# Relay12VDC.net
KiCad netlist of a schematic drawn in Altium Designer
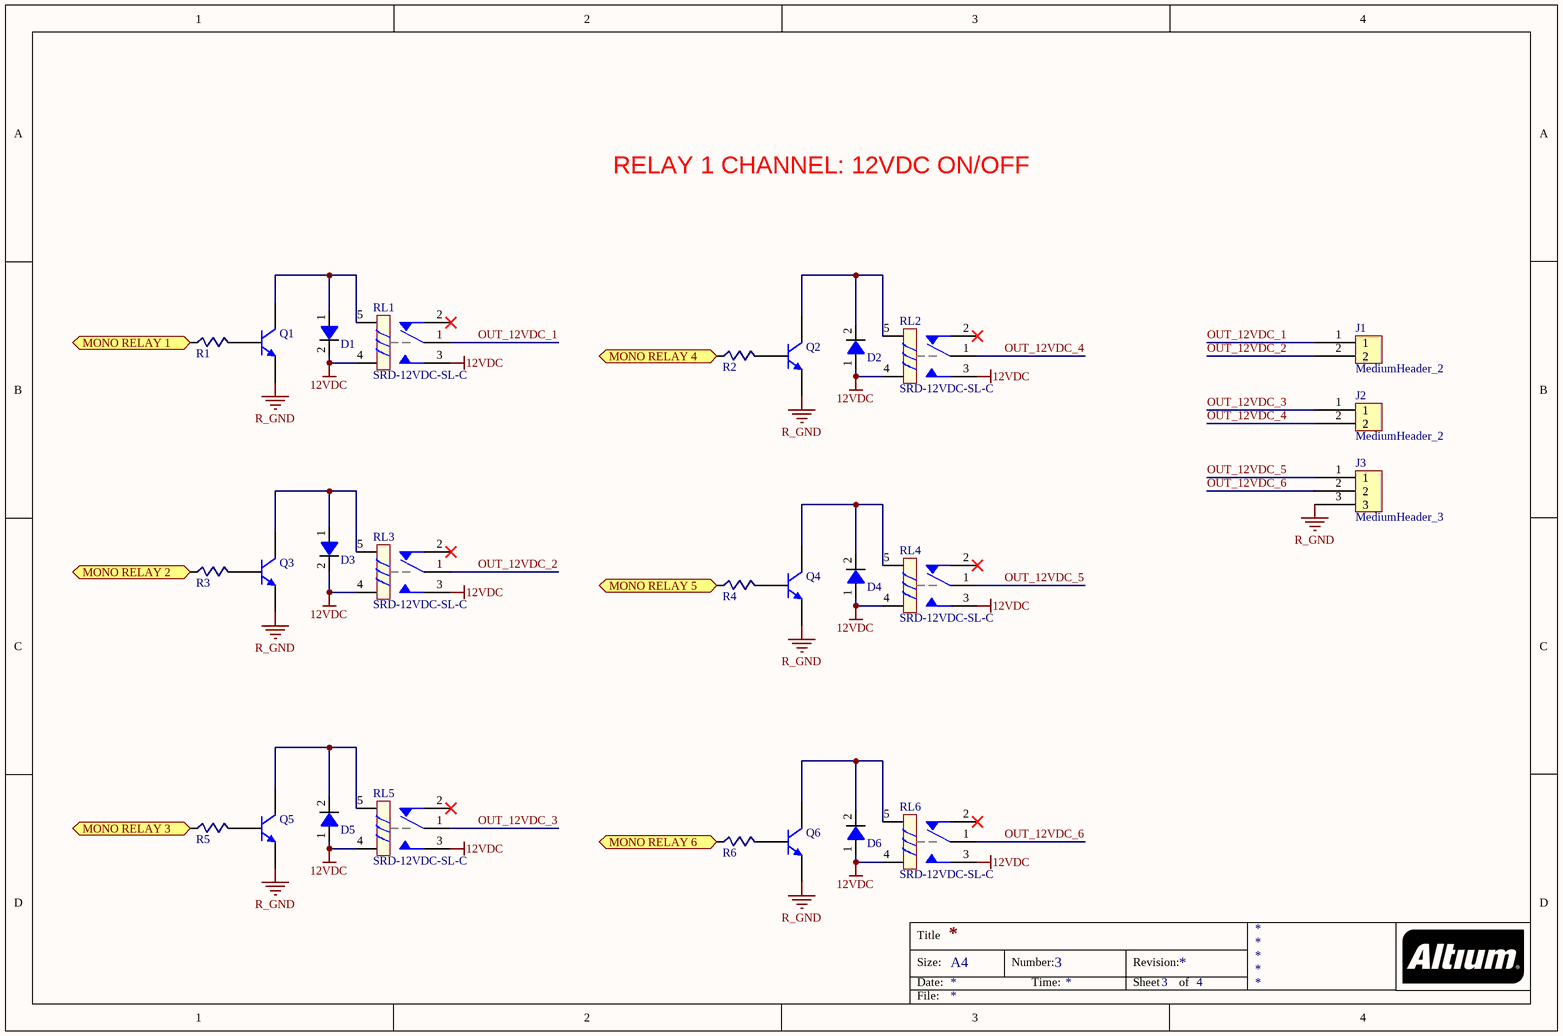
[diagram p0: Relay12VDC.SchDoc]

(export (version "E")
  (design (tool "Eeschema 10.0.6"))
  (components
    (comp (ref "D1")
      (value "M7 SMD")
      (footprint "Diode 1N4007 SMD")
      (description "DIODE GEN PURP 1KV 1A DO214AC")
      (libsource (lib "EngineersLife") (part "Diode_1N4007"))
    )
    (comp (ref "D2")
      (value "M7 SMD")
      (footprint "Diode 1N4007 SMD")
      (description "DIODE GEN PURP 1KV 1A DO214AC")
      (libsource (lib "EngineersLife") (part "Diode_1N4007"))
    )
    (comp (ref "D3")
      (value "M7 SMD")
      (footprint "Diode 1N4007 SMD")
      (description "DIODE GEN PURP 1KV 1A DO214AC")
      (libsource (lib "EngineersLife") (part "Diode_1N4007"))
    )
    (comp (ref "D4")
      (value "M7 SMD")
      (footprint "Diode 1N4007 SMD")
      (description "DIODE GEN PURP 1KV 1A DO214AC")
      (libsource (lib "EngineersLife") (part "Diode_1N4007"))
    )
    (comp (ref "D5")
      (value "M7 SMD")
      (footprint "Diode 1N4007 SMD")
      (description "DIODE GEN PURP 1KV 1A DO214AC")
      (libsource (lib "EngineersLife") (part "Diode_1N4007"))
    )
    (comp (ref "D6")
      (value "M7 SMD")
      (footprint "Diode 1N4007 SMD")
      (description "DIODE GEN PURP 1KV 1A DO214AC")
      (libsource (lib "EngineersLife") (part "Diode_1N4007"))
    )
    (comp (ref "J1")
      (value "MediumHeader_2")
      (footprint "Medium - Header 2")
      (libsource (lib "EngineersLife") (part "MediumHeader_2"))
    )
    (comp (ref "J2")
      (value "MediumHeader_2")
      (footprint "Medium - Header 2")
      (libsource (lib "EngineersLife") (part "MediumHeader_2"))
    )
    (comp (ref "J3")
      (value "MediumHeader_3")
      (footprint "Medium - Header 3")
      (libsource (lib "EngineersLife") (part "MediumHeader_3"))
    )
    (comp (ref "Q1")
      (value "MMBT3904")
      (footprint "SOT23_L_MOD")
      (description "TRANSISTOR GP NPN AMP SOT-23")
      (fields (field (name "PUBLISHER") "Altium Limited"))
      (libsource (lib "EngineersLife") (part "MMBT3904"))
    )
    (comp (ref "Q2")
      (value "MMBT3904")
      (footprint "SOT23_L_MOD")
      (description "TRANSISTOR GP NPN AMP SOT-23")
      (fields (field (name "PUBLISHER") "Altium Limited"))
      (libsource (lib "EngineersLife") (part "MMBT3904"))
    )
    (comp (ref "Q3")
      (value "MMBT3904")
      (footprint "SOT23_L_MOD")
      (description "TRANSISTOR GP NPN AMP SOT-23")
      (fields (field (name "PUBLISHER") "Altium Limited"))
      (libsource (lib "EngineersLife") (part "MMBT3904"))
    )
    (comp (ref "Q4")
      (value "MMBT3904")
      (footprint "SOT23_L_MOD")
      (description "TRANSISTOR GP NPN AMP SOT-23")
      (fields (field (name "PUBLISHER") "Altium Limited"))
      (libsource (lib "EngineersLife") (part "MMBT3904"))
    )
    (comp (ref "Q5")
      (value "MMBT3904")
      (footprint "SOT23_L_MOD")
      (description "TRANSISTOR GP NPN AMP SOT-23")
      (fields (field (name "PUBLISHER") "Altium Limited"))
      (libsource (lib "EngineersLife") (part "MMBT3904"))
    )
    (comp (ref "Q6")
      (value "MMBT3904")
      (footprint "SOT23_L_MOD")
      (description "TRANSISTOR GP NPN AMP SOT-23")
      (fields (field (name "PUBLISHER") "Altium Limited"))
      (libsource (lib "EngineersLife") (part "MMBT3904"))
    )
    (comp (ref "R1")
      (value "R_1K_0603")
      (footprint "RES-SMD-0603")
      (description "RES 1K OHM 1/10W 1% 0603 SMD")
      (libsource (lib "EngineersLife") (part "RES0603_1K"))
    )
    (comp (ref "R2")
      (value "R_1K_0603")
      (footprint "RES-SMD-0603")
      (description "RES 1K OHM 1/10W 1% 0603 SMD")
      (libsource (lib "EngineersLife") (part "RES0603_1K"))
    )
    (comp (ref "R3")
      (value "R_1K_0603")
      (footprint "RES-SMD-0603")
      (description "RES 1K OHM 1/10W 1% 0603 SMD")
      (libsource (lib "EngineersLife") (part "RES0603_1K"))
    )
    (comp (ref "R4")
      (value "R_1K_0603")
      (footprint "RES-SMD-0603")
      (description "RES 1K OHM 1/10W 1% 0603 SMD")
      (libsource (lib "EngineersLife") (part "RES0603_1K"))
    )
    (comp (ref "R5")
      (value "R_1K_0603")
      (footprint "RES-SMD-0603")
      (description "RES 1K OHM 1/10W 1% 0603 SMD")
      (libsource (lib "EngineersLife") (part "RES0603_1K"))
    )
    (comp (ref "R6")
      (value "R_1K_0603")
      (footprint "RES-SMD-0603")
      (description "RES 1K OHM 1/10W 1% 0603 SMD")
      (libsource (lib "EngineersLife") (part "RES0603_1K"))
    )
    (comp (ref "RL1")
      (value "SRD-12VDC-SL-C")
      (footprint "RELAY SRD-12VDC")
      (description "Relay SPDT,10A - 12VDC 5 Pin")
      (libsource (lib "EngineersLife") (part "RELAY SRD-12VDC"))
    )
    (comp (ref "RL2")
      (value "SRD-12VDC-SL-C")
      (footprint "RELAY SRD-12VDC")
      (description "Relay SPDT,10A - 12VDC 5 Pin")
      (libsource (lib "EngineersLife") (part "RELAY SRD-12VDC"))
    )
    (comp (ref "RL3")
      (value "SRD-12VDC-SL-C")
      (footprint "RELAY SRD-12VDC")
      (description "Relay SPDT,10A - 12VDC 5 Pin")
      (libsource (lib "EngineersLife") (part "RELAY SRD-12VDC"))
    )
    (comp (ref "RL4")
      (value "SRD-12VDC-SL-C")
      (footprint "RELAY SRD-12VDC")
      (description "Relay SPDT,10A - 12VDC 5 Pin")
      (libsource (lib "EngineersLife") (part "RELAY SRD-12VDC"))
    )
    (comp (ref "RL5")
      (value "SRD-12VDC-SL-C")
      (footprint "RELAY SRD-12VDC")
      (description "Relay SPDT,10A - 12VDC 5 Pin")
      (libsource (lib "EngineersLife") (part "RELAY SRD-12VDC"))
    )
    (comp (ref "RL6")
      (value "SRD-12VDC-SL-C")
      (footprint "RELAY SRD-12VDC")
      (description "Relay SPDT,10A - 12VDC 5 Pin")
      (libsource (lib "EngineersLife") (part "RELAY SRD-12VDC"))
    )
  )
  (nets
    (net (code "1") (name "/MONO RELAY 1") (class "Default")
      (node (ref "R1") (pin "1") (pinfunction "1_1") (pintype "passive"))
    )
    (net (code "2") (name "/MONO RELAY 2") (class "Default")
      (node (ref "R3") (pin "1") (pinfunction "1_1") (pintype "passive"))
    )
    (net (code "3") (name "/MONO RELAY 3") (class "Default")
      (node (ref "R5") (pin "1") (pinfunction "1_1") (pintype "passive"))
    )
    (net (code "4") (name "/MONO RELAY 4") (class "Default")
      (node (ref "R2") (pin "1") (pinfunction "1_1") (pintype "passive"))
    )
    (net (code "5") (name "/MONO RELAY 5") (class "Default")
      (node (ref "R4") (pin "1") (pinfunction "1_1") (pintype "passive"))
    )
    (net (code "6") (name "/MONO RELAY 6") (class "Default")
      (node (ref "R6") (pin "1") (pinfunction "1_1") (pintype "passive"))
    )
    (net (code "7") (name "/OUT_12VDC_1") (class "Default")
      (node (ref "J1") (pin "1") (pinfunction "1_1") (pintype "passive"))
      (node (ref "RL1") (pin "1") (pinfunction "1_1") (pintype "passive"))
    )
    (net (code "8") (name "/OUT_12VDC_2") (class "Default")
      (node (ref "J1") (pin "2") (pinfunction "2_2") (pintype "passive"))
      (node (ref "RL3") (pin "1") (pinfunction "1_1") (pintype "passive"))
    )
    (net (code "9") (name "/OUT_12VDC_3") (class "Default")
      (node (ref "J2") (pin "1") (pinfunction "1_1") (pintype "passive"))
      (node (ref "RL5") (pin "1") (pinfunction "1_1") (pintype "passive"))
    )
    (net (code "10") (name "/OUT_12VDC_4") (class "Default")
      (node (ref "J2") (pin "2") (pinfunction "2_2") (pintype "passive"))
      (node (ref "RL2") (pin "1") (pinfunction "1_1") (pintype "passive"))
    )
    (net (code "11") (name "/OUT_12VDC_5") (class "Default")
      (node (ref "J3") (pin "1") (pinfunction "1_1") (pintype "passive"))
      (node (ref "RL4") (pin "1") (pinfunction "1_1") (pintype "passive"))
    )
    (net (code "12") (name "/OUT_12VDC_6") (class "Default")
      (node (ref "J3") (pin "2") (pinfunction "2_2") (pintype "passive"))
      (node (ref "RL6") (pin "1") (pinfunction "1_1") (pintype "passive"))
    )
    (net (code "13") (name "12VDC") (class "Default")
      (node (ref "D1") (pin "2") (pinfunction "4_2") (pintype "passive"))
      (node (ref "D2") (pin "1") (pinfunction "3_1") (pintype "passive"))
      (node (ref "D3") (pin "2") (pinfunction "4_2") (pintype "passive"))
      (node (ref "D4") (pin "1") (pinfunction "3_1") (pintype "passive"))
      (node (ref "D5") (pin "1") (pinfunction "3_1") (pintype "passive"))
      (node (ref "D6") (pin "1") (pinfunction "3_1") (pintype "passive"))
      (node (ref "RL1") (pin "3") (pinfunction "3_3") (pintype "passive"))
      (node (ref "RL1") (pin "4") (pinfunction "4_4") (pintype "passive"))
      (node (ref "RL2") (pin "3") (pinfunction "3_3") (pintype "passive"))
      (node (ref "RL2") (pin "4") (pinfunction "4_4") (pintype "passive"))
      (node (ref "RL3") (pin "3") (pinfunction "3_3") (pintype "passive"))
      (node (ref "RL3") (pin "4") (pinfunction "4_4") (pintype "passive"))
      (node (ref "RL4") (pin "3") (pinfunction "3_3") (pintype "passive"))
      (node (ref "RL4") (pin "4") (pinfunction "4_4") (pintype "passive"))
      (node (ref "RL5") (pin "3") (pinfunction "3_3") (pintype "passive"))
      (node (ref "RL5") (pin "4") (pinfunction "4_4") (pintype "passive"))
      (node (ref "RL6") (pin "3") (pinfunction "3_3") (pintype "passive"))
      (node (ref "RL6") (pin "4") (pinfunction "4_4") (pintype "passive"))
    )
    (net (code "14") (name "Net-(D1-3)") (class "Default")
      (node (ref "D1") (pin "1") (pinfunction "3_1") (pintype "passive"))
      (node (ref "Q1") (pin "3") (pinfunction "C_3") (pintype "passive"))
      (node (ref "RL1") (pin "5") (pinfunction "5_5") (pintype "passive"))
    )
    (net (code "15") (name "Net-(D2-4)") (class "Default")
      (node (ref "D2") (pin "2") (pinfunction "4_2") (pintype "passive"))
      (node (ref "Q2") (pin "3") (pinfunction "C_3") (pintype "passive"))
      (node (ref "RL2") (pin "5") (pinfunction "5_5") (pintype "passive"))
    )
    (net (code "16") (name "Net-(D3-3)") (class "Default")
      (node (ref "D3") (pin "1") (pinfunction "3_1") (pintype "passive"))
      (node (ref "Q3") (pin "3") (pinfunction "C_3") (pintype "passive"))
      (node (ref "RL3") (pin "5") (pinfunction "5_5") (pintype "passive"))
    )
    (net (code "17") (name "Net-(D4-4)") (class "Default")
      (node (ref "D4") (pin "2") (pinfunction "4_2") (pintype "passive"))
      (node (ref "Q4") (pin "3") (pinfunction "C_3") (pintype "passive"))
      (node (ref "RL4") (pin "5") (pinfunction "5_5") (pintype "passive"))
    )
    (net (code "18") (name "Net-(D5-4)") (class "Default")
      (node (ref "D5") (pin "2") (pinfunction "4_2") (pintype "passive"))
      (node (ref "Q5") (pin "3") (pinfunction "C_3") (pintype "passive"))
      (node (ref "RL5") (pin "5") (pinfunction "5_5") (pintype "passive"))
    )
    (net (code "19") (name "Net-(D6-4)") (class "Default")
      (node (ref "D6") (pin "2") (pinfunction "4_2") (pintype "passive"))
      (node (ref "Q6") (pin "3") (pinfunction "C_3") (pintype "passive"))
      (node (ref "RL6") (pin "5") (pinfunction "5_5") (pintype "passive"))
    )
    (net (code "20") (name "Net-(Q1-B)") (class "Default")
      (node (ref "Q1") (pin "1") (pinfunction "B_1") (pintype "passive"))
      (node (ref "R1") (pin "2") (pinfunction "2_2") (pintype "passive"))
    )
    (net (code "21") (name "Net-(Q2-B)") (class "Default")
      (node (ref "Q2") (pin "1") (pinfunction "B_1") (pintype "passive"))
      (node (ref "R2") (pin "2") (pinfunction "2_2") (pintype "passive"))
    )
    (net (code "22") (name "Net-(Q3-B)") (class "Default")
      (node (ref "Q3") (pin "1") (pinfunction "B_1") (pintype "passive"))
      (node (ref "R3") (pin "2") (pinfunction "2_2") (pintype "passive"))
    )
    (net (code "23") (name "Net-(Q4-B)") (class "Default")
      (node (ref "Q4") (pin "1") (pinfunction "B_1") (pintype "passive"))
      (node (ref "R4") (pin "2") (pinfunction "2_2") (pintype "passive"))
    )
    (net (code "24") (name "Net-(Q5-B)") (class "Default")
      (node (ref "Q5") (pin "1") (pinfunction "B_1") (pintype "passive"))
      (node (ref "R5") (pin "2") (pinfunction "2_2") (pintype "passive"))
    )
    (net (code "25") (name "Net-(Q6-B)") (class "Default")
      (node (ref "Q6") (pin "1") (pinfunction "B_1") (pintype "passive"))
      (node (ref "R6") (pin "2") (pinfunction "2_2") (pintype "passive"))
    )
    (net (code "26") (name "R_GND") (class "Default")
      (node (ref "J3") (pin "3") (pinfunction "3_3") (pintype "passive"))
      (node (ref "Q1") (pin "2") (pinfunction "E_2") (pintype "passive"))
      (node (ref "Q2") (pin "2") (pinfunction "E_2") (pintype "passive"))
      (node (ref "Q3") (pin "2") (pinfunction "E_2") (pintype "passive"))
      (node (ref "Q4") (pin "2") (pinfunction "E_2") (pintype "passive"))
      (node (ref "Q5") (pin "2") (pinfunction "E_2") (pintype "passive"))
      (node (ref "Q6") (pin "2") (pinfunction "E_2") (pintype "passive"))
    )
    (net (code "27") (name "unconnected-(RL1-Pad2)") (class "Default")
      (node (ref "RL1") (pin "2") (pinfunction "2_2") (pintype "passive+no_connect"))
    )
    (net (code "28") (name "unconnected-(RL2-Pad2)") (class "Default")
      (node (ref "RL2") (pin "2") (pinfunction "2_2") (pintype "passive+no_connect"))
    )
    (net (code "29") (name "unconnected-(RL3-Pad2)") (class "Default")
      (node (ref "RL3") (pin "2") (pinfunction "2_2") (pintype "passive+no_connect"))
    )
    (net (code "30") (name "unconnected-(RL4-Pad2)") (class "Default")
      (node (ref "RL4") (pin "2") (pinfunction "2_2") (pintype "passive+no_connect"))
    )
    (net (code "31") (name "unconnected-(RL5-Pad2)") (class "Default")
      (node (ref "RL5") (pin "2") (pinfunction "2_2") (pintype "passive+no_connect"))
    )
    (net (code "32") (name "unconnected-(RL6-Pad2)") (class "Default")
      (node (ref "RL6") (pin "2") (pinfunction "2_2") (pintype "passive+no_connect"))
    )
  )
)
